# ProProject_stm32f103c8t6__2024-05-02.net
KiCad netlist of a schematic drawn in EasyEDA Pro
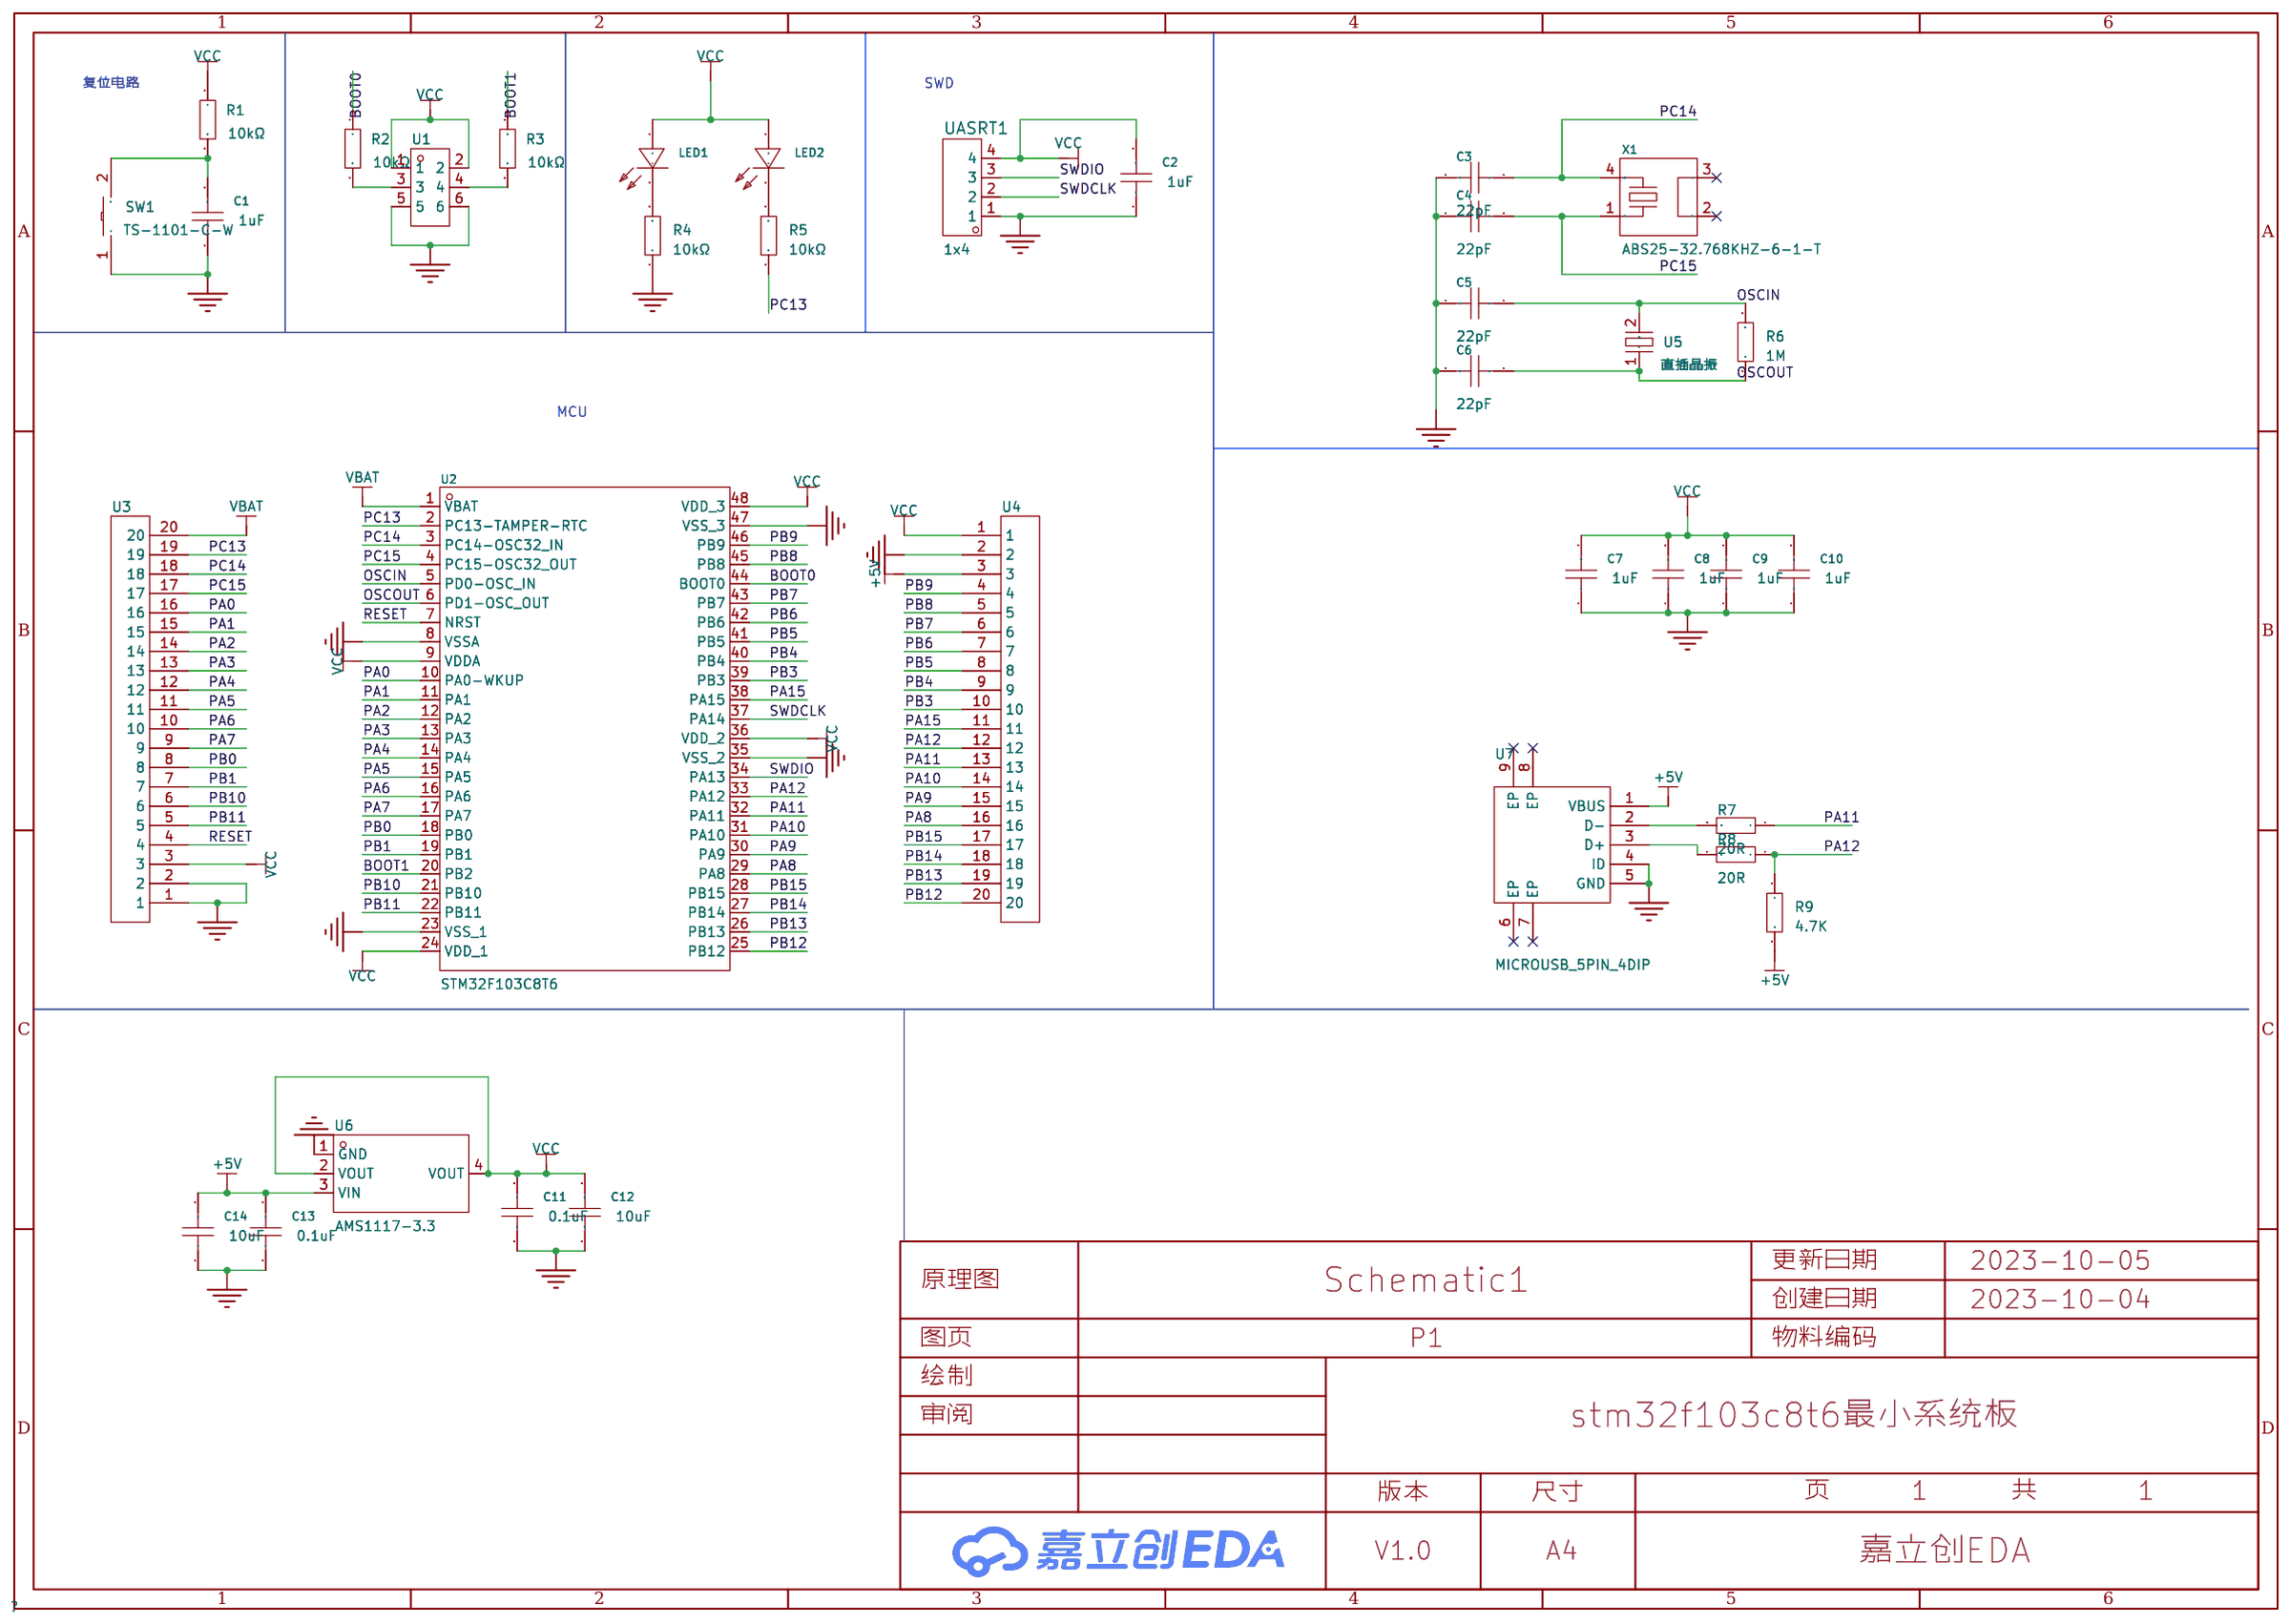
[diagram p0: schematic sheet]

(export (version "E")
  (design (tool "Eeschema 10.0.6"))
  (components
    (comp (ref "C1")
      (value "1uF")
      (footprint "easyedapro:C0603")
      (description "容值:4.7uF;额定电压:25V;材质(温度系数):X5R;")
      (fields
        (field (name "Manufacturer Part") "TCC0603X5R475K250CT")
        (field (name "Manufacturer") "CCTC(三环)")
      )
      (libsource (lib "easyedapro") (part "TCC0603X5R475K250CT"))
    )
    (comp (ref "C2")
      (value "1uF")
      (footprint "easyedapro:C0603")
      (description "容值:4.7uF;额定电压:25V;材质(温度系数):X5R;")
      (fields
        (field (name "Manufacturer Part") "TCC0603X5R475K250CT")
        (field (name "Manufacturer") "CCTC(三环)")
      )
      (libsource (lib "easyedapro") (part "TCC0603X5R475K250CT"))
    )
    (comp (ref "C3")
      (value "22pF")
      (footprint "easyedapro:C0603")
      (description "容值:4.7uF;额定电压:25V;材质(温度系数):X5R;")
      (fields
        (field (name "Manufacturer Part") "TCC0603X5R475K250CT")
        (field (name "Manufacturer") "CCTC(三环)")
      )
      (libsource (lib "easyedapro") (part "TCC0603X5R475K250CT"))
    )
    (comp (ref "C4")
      (value "22pF")
      (footprint "easyedapro:C0603")
      (description "容值:4.7uF;额定电压:25V;材质(温度系数):X5R;")
      (fields
        (field (name "Manufacturer Part") "TCC0603X5R475K250CT")
        (field (name "Manufacturer") "CCTC(三环)")
      )
      (libsource (lib "easyedapro") (part "TCC0603X5R475K250CT"))
    )
    (comp (ref "C5")
      (value "22pF")
      (footprint "easyedapro:C0603")
      (description "容值:4.7uF;额定电压:25V;材质(温度系数):X5R;")
      (fields
        (field (name "Manufacturer Part") "TCC0603X5R475K250CT")
        (field (name "Manufacturer") "CCTC(三环)")
      )
      (libsource (lib "easyedapro") (part "TCC0603X5R475K250CT"))
    )
    (comp (ref "C6")
      (value "22pF")
      (footprint "easyedapro:C0603")
      (description "容值:4.7uF;额定电压:25V;材质(温度系数):X5R;")
      (fields
        (field (name "Manufacturer Part") "TCC0603X5R475K250CT")
        (field (name "Manufacturer") "CCTC(三环)")
      )
      (libsource (lib "easyedapro") (part "TCC0603X5R475K250CT"))
    )
    (comp (ref "C7")
      (value "1uF")
      (footprint "easyedapro:C0603")
      (description "容值:4.7uF;额定电压:25V;材质(温度系数):X5R;")
      (fields
        (field (name "Manufacturer Part") "TCC0603X5R475K250CT")
        (field (name "Manufacturer") "CCTC(三环)")
      )
      (libsource (lib "easyedapro") (part "TCC0603X5R475K250CT"))
    )
    (comp (ref "C8")
      (value "1uF")
      (footprint "easyedapro:C0603")
      (description "容值:4.7uF;额定电压:25V;材质(温度系数):X5R;")
      (fields
        (field (name "Manufacturer Part") "TCC0603X5R475K250CT")
        (field (name "Manufacturer") "CCTC(三环)")
      )
      (libsource (lib "easyedapro") (part "TCC0603X5R475K250CT"))
    )
    (comp (ref "C9")
      (value "1uF")
      (footprint "easyedapro:C0603")
      (description "容值:4.7uF;额定电压:25V;材质(温度系数):X5R;")
      (fields
        (field (name "Manufacturer Part") "TCC0603X5R475K250CT")
        (field (name "Manufacturer") "CCTC(三环)")
      )
      (libsource (lib "easyedapro") (part "TCC0603X5R475K250CT"))
    )
    (comp (ref "C10")
      (value "1uF")
      (footprint "easyedapro:C0603")
      (description "容值:4.7uF;额定电压:25V;材质(温度系数):X5R;")
      (fields
        (field (name "Manufacturer Part") "TCC0603X5R475K250CT")
        (field (name "Manufacturer") "CCTC(三环)")
      )
      (libsource (lib "easyedapro") (part "TCC0603X5R475K250CT"))
    )
    (comp (ref "C11")
      (value "0.1uF")
      (footprint "easyedapro:C0603")
      (description "容值:4.7uF;额定电压:25V;材质(温度系数):X5R;")
      (fields
        (field (name "Manufacturer Part") "TCC0603X5R475K250CT")
        (field (name "Manufacturer") "CCTC(三环)")
      )
      (libsource (lib "easyedapro") (part "TCC0603X5R475K250CT"))
    )
    (comp (ref "C12")
      (value "10uF")
      (footprint "easyedapro:C0603")
      (description "容值:4.7uF;额定电压:25V;材质(温度系数):X5R;")
      (fields
        (field (name "Manufacturer Part") "TCC0603X5R475K250CT")
        (field (name "Manufacturer") "CCTC(三环)")
      )
      (libsource (lib "easyedapro") (part "TCC0603X5R475K250CT"))
    )
    (comp (ref "C13")
      (value "0.1uF")
      (footprint "easyedapro:C0603")
      (description "容值:4.7uF;额定电压:25V;材质(温度系数):X5R;")
      (fields
        (field (name "Manufacturer Part") "TCC0603X5R475K250CT")
        (field (name "Manufacturer") "CCTC(三环)")
      )
      (libsource (lib "easyedapro") (part "TCC0603X5R475K250CT"))
    )
    (comp (ref "C14")
      (value "10uF")
      (footprint "easyedapro:C0603")
      (description "容值:4.7uF;额定电压:25V;材质(温度系数):X5R;")
      (fields
        (field (name "Manufacturer Part") "TCC0603X5R475K250CT")
        (field (name "Manufacturer") "CCTC(三环)")
      )
      (libsource (lib "easyedapro") (part "TCC0603X5R475K250CT"))
    )
    (comp (ref "LED1")
      (value "KT-0805G")
      (footprint "easyedapro:LED0805-R-RD")
      (description "发光颜色:翠绿;二极管配置:-;透镜颜色:-;主波长:-;色温:-;光通量(25℃时):-;发光强度:-;功率:-;发光角度:-;安装方式:-;工作温度:-;")
      (fields (field (name "Manufacturer") "KENTO"))
      (libsource (lib "easyedapro") (part "0805G (Green)"))
    )
    (comp (ref "LED2")
      (value "KT-0805G")
      (footprint "easyedapro:LED0805-R-RD")
      (description "发光颜色:翠绿;二极管配置:-;透镜颜色:-;主波长:-;色温:-;光通量(25°C时):-;发光强度:-;功率:-;发光角度:-;安装方式:-;工作温度:-;")
      (fields (field (name "Manufacturer") "KENTO"))
      (libsource (lib "easyedapro") (part "0805G (Green)"))
    )
    (comp (ref "R1")
      (value "10kΩ")
      (footprint "easyedapro:R0603")
      (description "电阻类型:厚膜电阻;阻值:10kΩ;精度:±1%;功率:100mW;")
      (fields
        (field (name "Manufacturer Part") "0603WAF1002T5E")
        (field (name "Manufacturer") "UNI-ROYAL(厚声)")
      )
      (libsource (lib "easyedapro") (part "0603WAF1002T5E"))
    )
    (comp (ref "R2")
      (value "10kΩ")
      (footprint "easyedapro:R0603")
      (description "电阻类型:厚膜电阻;阻值:10kΩ;精度:±1%;功率:100mW;")
      (fields
        (field (name "Manufacturer Part") "0603WAF1002T5E")
        (field (name "Manufacturer") "UNI-ROYAL(厚声)")
      )
      (libsource (lib "easyedapro") (part "0603WAF1002T5E"))
    )
    (comp (ref "R3")
      (value "10kΩ")
      (footprint "easyedapro:R0603")
      (description "电阻类型:厚膜电阻;阻值:10kΩ;精度:±1%;功率:100mW;")
      (fields
        (field (name "Manufacturer Part") "0603WAF1002T5E")
        (field (name "Manufacturer") "UNI-ROYAL(厚声)")
      )
      (libsource (lib "easyedapro") (part "0603WAF1002T5E"))
    )
    (comp (ref "R4")
      (value "10kΩ")
      (footprint "easyedapro:R0603")
      (description "电阻类型:厚膜电阻;阻值:10kΩ;精度:±1%;功率:100mW;")
      (fields
        (field (name "Manufacturer Part") "0603WAF1002T5E")
        (field (name "Manufacturer") "UNI-ROYAL(厚声)")
      )
      (libsource (lib "easyedapro") (part "0603WAF1002T5E"))
    )
    (comp (ref "R5")
      (value "10kΩ")
      (footprint "easyedapro:R0603")
      (description "电阻类型:厚膜电阻;阻值:10kΩ;精度:±1%;功率:100mW;")
      (fields
        (field (name "Manufacturer Part") "0603WAF1002T5E")
        (field (name "Manufacturer") "UNI-ROYAL(厚声)")
      )
      (libsource (lib "easyedapro") (part "0603WAF1002T5E"))
    )
    (comp (ref "R6")
      (value "1M")
      (footprint "easyedapro:R0603")
      (description "电阻类型:厚膜电阻;阻值:10kΩ;精度:±1%;功率:100mW;")
      (fields
        (field (name "Manufacturer Part") "0603WAF1002T5E")
        (field (name "Manufacturer") "UNI-ROYAL(厚声)")
      )
      (libsource (lib "easyedapro") (part "0603WAF1002T5E"))
    )
    (comp (ref "R7")
      (value "20R")
      (footprint "easyedapro:R0603")
      (description "电阻类型:厚膜电阻;阻值:10kΩ;精度:±1%;功率:100mW;")
      (fields
        (field (name "Manufacturer Part") "0603WAF1002T5E")
        (field (name "Manufacturer") "UNI-ROYAL(厚声)")
      )
      (libsource (lib "easyedapro") (part "0603WAF1002T5E"))
    )
    (comp (ref "R8")
      (value "20R")
      (footprint "easyedapro:R0603")
      (description "电阻类型:厚膜电阻;阻值:10kΩ;精度:±1%;功率:100mW;")
      (fields
        (field (name "Manufacturer Part") "0603WAF1002T5E")
        (field (name "Manufacturer") "UNI-ROYAL(厚声)")
      )
      (libsource (lib "easyedapro") (part "0603WAF1002T5E"))
    )
    (comp (ref "R9")
      (value "4.7K")
      (footprint "easyedapro:R0603")
      (description "电阻类型:厚膜电阻;阻值:10kΩ;精度:±1%;功率:100mW;")
      (fields
        (field (name "Manufacturer Part") "0603WAF1002T5E")
        (field (name "Manufacturer") "UNI-ROYAL(厚声)")
      )
      (libsource (lib "easyedapro") (part "0603WAF1002T5E"))
    )
    (comp (ref "SW1")
      (value "TS-1101-C-W")
      (footprint "easyedapro:SW-SMD_L6.0-W3.3-LS8.0")
      (description "触点电流:50mA;额定电压(AC):-;额定电压(DC):12V;额定功率:-;绝缘电阻:-;电路结构:单刀单掷;安装方式:立贴;带灯:无;作用力:260gf;机械寿命:5万次;带支架:否;")
      (fields (field (name "Manufacturer") "XKB Connectivity(中国星坤)"))
      (libsource (lib "easyedapro") (part "TS-1101-C-W"))
    )
    (comp (ref "U1")
      (value "2.54mm,2X3,短针针长3mm,长针针长6mm")
      (footprint "easyedapro:HDR-TH_6P-P2.54-V-M-R2-C3-S2.54-2")
      (libsource (lib "easyedapro") (part "2.54MM,2X3,短针针长3MM,长针针长6MM"))
    )
    (comp (ref "U2")
      (value "STM32F103C8T6")
      (footprint "easyedapro:LQFP-48_L7.0-W7.0-P0.50-LS9.0-BL")
      (fields (field (name "Manufacturer") "ST(意法半导体)"))
      (libsource (lib "easyedapro") (part "STM32F103C8T6"))
    )
    (comp (ref "U3")
      (value "~")
      (footprint "easyedapro:HDR1X20")
      (libsource (lib "easyedapro") (part "1X20"))
    )
    (comp (ref "U4")
      (value "~")
      (footprint "easyedapro:HDR1X20")
      (libsource (lib "easyedapro") (part "1X20"))
    )
    (comp (ref "U5")
      (value "直插晶振")
      (footprint "easyedapro:HC-49S_L11.0-W4.7-P4.88")
      (libsource (lib "easyedapro") (part "直插晶振"))
    )
    (comp (ref "U6")
      (value "AMS1117-3.3")
      (footprint "easyedapro:SOT-223-3_L6.5-W3.4-P2.30-LS7.0-BR")
      (description "输出类型:固定;输出极性:正;最大输入电压:-;输出电压:3.3V;输出电流:1A;电源纹波抑制比(PSRR):72dB@(120Hz);")
      (fields (field (name "Manufacturer") "AMS"))
      (libsource (lib "easyedapro") (part "AMS1117-3.3"))
    )
    (comp (ref "U7")
      (value "MICROUSB_5PIN_4DIP")
      (footprint "easyedapro:MICRO-USB-SMD_U254-051N-4BH806")
      (libsource (lib "easyedapro") (part "MICROUSB_5PIN_4DIP"))
    )
    (comp (ref "UASRT1")
      (value "1x4")
      (footprint "easyedapro:HDR-TH_4P-P2.54-V-M-1")
      (fields
        (field (name "Manufacturer Part") "Headers  Pins 1*4P")
        (field (name "Manufacturer") "ReliaPro")
      )
      (libsource (lib "easyedapro") (part "1x4"))
    )
    (comp (ref "X1")
      (value "ABS25-32.768KHZ-6-1-T")
      (footprint "easyedapro:SOJ-4_L8.4-W3.8-P5.5-BL")
      (fields (field (name "Manufacturer") "ABRACON"))
      (libsource (lib "easyedapro") (part "ABS25-32.768KHZ-6-1-T"))
    )
  )
  (nets
    (net (code "1") (name "+5V") (class "Default")
      (node (ref "C13") (pin "2") (pinfunction "2_2") (pintype "input"))
      (node (ref "C14") (pin "2") (pinfunction "2_2") (pintype "input"))
      (node (ref "R9") (pin "2") (pinfunction "2_2") (pintype "input"))
      (node (ref "U4") (pin "3") (pinfunction "3_3") (pintype "input"))
      (node (ref "U6") (pin "3") (pinfunction "VIN_3") (pintype "input"))
      (node (ref "U7") (pin "1") (pinfunction "VBUS_1") (pintype "input"))
    )
    (net (code "2") (name "/BOOT0") (class "Default")
      (node (ref "R2") (pin "1") (pinfunction "1_1") (pintype "input"))
      (node (ref "U2") (pin "44") (pinfunction "BOOT0_44") (pintype "input"))
    )
    (net (code "3") (name "/BOOT1") (class "Default")
      (node (ref "R3") (pin "1") (pinfunction "1_1") (pintype "input"))
      (node (ref "U2") (pin "20") (pinfunction "PB2_20") (pintype "input"))
    )
    (net (code "4") (name "/OSCIN") (class "Default")
      (node (ref "C5") (pin "1") (pinfunction "1_1") (pintype "input"))
      (node (ref "R6") (pin "2") (pinfunction "2_2") (pintype "input"))
      (node (ref "U2") (pin "5") (pinfunction "PD0-OSC_IN_5") (pintype "input"))
      (node (ref "U5") (pin "2") (pinfunction "GND_2") (pintype "input"))
    )
    (net (code "5") (name "/OSCOUT") (class "Default")
      (node (ref "C6") (pin "1") (pinfunction "1_1") (pintype "input"))
      (node (ref "R6") (pin "1") (pinfunction "1_1") (pintype "input"))
      (node (ref "U2") (pin "6") (pinfunction "PD1-OSC_OUT_6") (pintype "input"))
      (node (ref "U5") (pin "1") (pinfunction "1_1") (pintype "input"))
    )
    (net (code "6") (name "/PA0") (class "Default")
      (node (ref "U2") (pin "10") (pinfunction "PA0-WKUP_10") (pintype "input"))
      (node (ref "U3") (pin "16") (pinfunction "16_16") (pintype "input"))
    )
    (net (code "7") (name "/PA1") (class "Default")
      (node (ref "U2") (pin "11") (pinfunction "PA1_11") (pintype "input"))
      (node (ref "U3") (pin "15") (pinfunction "15_15") (pintype "input"))
    )
    (net (code "8") (name "/PA2") (class "Default")
      (node (ref "U2") (pin "12") (pinfunction "PA2_12") (pintype "input"))
      (node (ref "U3") (pin "14") (pinfunction "14_14") (pintype "input"))
    )
    (net (code "9") (name "/PA3") (class "Default")
      (node (ref "U2") (pin "13") (pinfunction "PA3_13") (pintype "input"))
      (node (ref "U3") (pin "13") (pinfunction "13_13") (pintype "input"))
    )
    (net (code "10") (name "/PA4") (class "Default")
      (node (ref "U2") (pin "14") (pinfunction "PA4_14") (pintype "input"))
      (node (ref "U3") (pin "12") (pinfunction "12_12") (pintype "input"))
    )
    (net (code "11") (name "/PA5") (class "Default")
      (node (ref "U2") (pin "15") (pinfunction "PA5_15") (pintype "input"))
      (node (ref "U3") (pin "11") (pinfunction "11_11") (pintype "input"))
    )
    (net (code "12") (name "/PA6") (class "Default")
      (node (ref "U2") (pin "16") (pinfunction "PA6_16") (pintype "input"))
      (node (ref "U3") (pin "10") (pinfunction "10_10") (pintype "input"))
    )
    (net (code "13") (name "/PA7") (class "Default")
      (node (ref "U2") (pin "17") (pinfunction "PA7_17") (pintype "input"))
      (node (ref "U3") (pin "9") (pinfunction "9_9") (pintype "input"))
    )
    (net (code "14") (name "/PA8") (class "Default")
      (node (ref "U2") (pin "29") (pinfunction "PA8_29") (pintype "input"))
      (node (ref "U4") (pin "16") (pinfunction "16_16") (pintype "input"))
    )
    (net (code "15") (name "/PA9") (class "Default")
      (node (ref "U2") (pin "30") (pinfunction "PA9_30") (pintype "input"))
      (node (ref "U4") (pin "15") (pinfunction "15_15") (pintype "input"))
    )
    (net (code "16") (name "/PA10") (class "Default")
      (node (ref "U2") (pin "31") (pinfunction "PA10_31") (pintype "input"))
      (node (ref "U4") (pin "14") (pinfunction "14_14") (pintype "input"))
    )
    (net (code "17") (name "/PA11") (class "Default")
      (node (ref "R7") (pin "1") (pinfunction "1_1") (pintype "input"))
      (node (ref "U2") (pin "32") (pinfunction "PA11_32") (pintype "input"))
      (node (ref "U4") (pin "13") (pinfunction "13_13") (pintype "input"))
    )
    (net (code "18") (name "/PA12") (class "Default")
      (node (ref "R8") (pin "1") (pinfunction "1_1") (pintype "input"))
      (node (ref "R9") (pin "1") (pinfunction "1_1") (pintype "input"))
      (node (ref "U2") (pin "33") (pinfunction "PA12_33") (pintype "input"))
      (node (ref "U4") (pin "12") (pinfunction "12_12") (pintype "input"))
    )
    (net (code "19") (name "/PA15") (class "Default")
      (node (ref "U2") (pin "38") (pinfunction "PA15_38") (pintype "input"))
      (node (ref "U4") (pin "11") (pinfunction "11_11") (pintype "input"))
    )
    (net (code "20") (name "/PB0") (class "Default")
      (node (ref "U2") (pin "18") (pinfunction "PB0_18") (pintype "input"))
      (node (ref "U3") (pin "8") (pinfunction "8_8") (pintype "input"))
    )
    (net (code "21") (name "/PB1") (class "Default")
      (node (ref "U2") (pin "19") (pinfunction "PB1_19") (pintype "input"))
      (node (ref "U3") (pin "7") (pinfunction "7_7") (pintype "input"))
    )
    (net (code "22") (name "/PB3") (class "Default")
      (node (ref "U2") (pin "39") (pinfunction "PB3_39") (pintype "input"))
      (node (ref "U4") (pin "10") (pinfunction "10_10") (pintype "input"))
    )
    (net (code "23") (name "/PB4") (class "Default")
      (node (ref "U2") (pin "40") (pinfunction "PB4_40") (pintype "input"))
      (node (ref "U4") (pin "9") (pinfunction "9_9") (pintype "input"))
    )
    (net (code "24") (name "/PB5") (class "Default")
      (node (ref "U2") (pin "41") (pinfunction "PB5_41") (pintype "input"))
      (node (ref "U4") (pin "8") (pinfunction "8_8") (pintype "input"))
    )
    (net (code "25") (name "/PB6") (class "Default")
      (node (ref "U2") (pin "42") (pinfunction "PB6_42") (pintype "input"))
      (node (ref "U4") (pin "7") (pinfunction "7_7") (pintype "input"))
    )
    (net (code "26") (name "/PB7") (class "Default")
      (node (ref "U2") (pin "43") (pinfunction "PB7_43") (pintype "input"))
      (node (ref "U4") (pin "6") (pinfunction "6_6") (pintype "input"))
    )
    (net (code "27") (name "/PB8") (class "Default")
      (node (ref "U2") (pin "45") (pinfunction "PB8_45") (pintype "input"))
      (node (ref "U4") (pin "5") (pinfunction "5_5") (pintype "input"))
    )
    (net (code "28") (name "/PB9") (class "Default")
      (node (ref "U2") (pin "46") (pinfunction "PB9_46") (pintype "input"))
      (node (ref "U4") (pin "4") (pinfunction "4_4") (pintype "input"))
    )
    (net (code "29") (name "/PB10") (class "Default")
      (node (ref "U2") (pin "21") (pinfunction "PB10_21") (pintype "input"))
      (node (ref "U3") (pin "6") (pinfunction "6_6") (pintype "input"))
    )
    (net (code "30") (name "/PB11") (class "Default")
      (node (ref "U2") (pin "22") (pinfunction "PB11_22") (pintype "input"))
      (node (ref "U3") (pin "5") (pinfunction "5_5") (pintype "input"))
    )
    (net (code "31") (name "/PB12") (class "Default")
      (node (ref "U2") (pin "25") (pinfunction "PB12_25") (pintype "input"))
      (node (ref "U4") (pin "20") (pinfunction "20_20") (pintype "input"))
    )
    (net (code "32") (name "/PB13") (class "Default")
      (node (ref "U2") (pin "26") (pinfunction "PB13_26") (pintype "input"))
      (node (ref "U4") (pin "19") (pinfunction "19_19") (pintype "input"))
    )
    (net (code "33") (name "/PB14") (class "Default")
      (node (ref "U2") (pin "27") (pinfunction "PB14_27") (pintype "input"))
      (node (ref "U4") (pin "18") (pinfunction "18_18") (pintype "input"))
    )
    (net (code "34") (name "/PB15") (class "Default")
      (node (ref "U2") (pin "28") (pinfunction "PB15_28") (pintype "input"))
      (node (ref "U4") (pin "17") (pinfunction "17_17") (pintype "input"))
    )
    (net (code "35") (name "/PC13") (class "Default")
      (node (ref "R5") (pin "1") (pinfunction "1_1") (pintype "input"))
      (node (ref "U2") (pin "2") (pinfunction "PC13-TAMPER-RTC_2") (pintype "input"))
      (node (ref "U3") (pin "19") (pinfunction "19_19") (pintype "input"))
    )
    (net (code "36") (name "/PC14") (class "Default")
      (node (ref "C3") (pin "1") (pinfunction "1_1") (pintype "input"))
      (node (ref "U2") (pin "3") (pinfunction "PC14-OSC32_IN_3") (pintype "input"))
      (node (ref "U3") (pin "18") (pinfunction "18_18") (pintype "input"))
      (node (ref "X1") (pin "4") (pinfunction "GND_4") (pintype "input"))
    )
    (net (code "37") (name "/PC15") (class "Default")
      (node (ref "C4") (pin "1") (pinfunction "1_1") (pintype "input"))
      (node (ref "U2") (pin "4") (pinfunction "PC15-OSC32_OUT_4") (pintype "input"))
      (node (ref "U3") (pin "17") (pinfunction "17_17") (pintype "input"))
      (node (ref "X1") (pin "1") (pinfunction "1_1") (pintype "input"))
    )
    (net (code "38") (name "/RESET") (class "Default")
      (node (ref "U2") (pin "7") (pinfunction "NRST_7") (pintype "input"))
      (node (ref "U3") (pin "4") (pinfunction "4_4") (pintype "input"))
    )
    (net (code "39") (name "/SWDCLK") (class "Default")
      (node (ref "U2") (pin "37") (pinfunction "PA14_37") (pintype "input"))
      (node (ref "UASRT1") (pin "2") (pinfunction "2_2") (pintype "input"))
    )
    (net (code "40") (name "/SWDIO") (class "Default")
      (node (ref "U2") (pin "34") (pinfunction "PA13_34") (pintype "input"))
      (node (ref "UASRT1") (pin "3") (pinfunction "3_3") (pintype "input"))
    )
    (net (code "41") (name "GND") (class "Default")
      (node (ref "C1") (pin "1") (pinfunction "1_1") (pintype "input"))
      (node (ref "C10") (pin "1") (pinfunction "1_1") (pintype "input"))
      (node (ref "C11") (pin "1") (pinfunction "1_1") (pintype "input"))
      (node (ref "C12") (pin "1") (pinfunction "1_1") (pintype "input"))
      (node (ref "C13") (pin "1") (pinfunction "1_1") (pintype "input"))
      (node (ref "C14") (pin "1") (pinfunction "1_1") (pintype "input"))
      (node (ref "C2") (pin "1") (pinfunction "1_1") (pintype "input"))
      (node (ref "C3") (pin "2") (pinfunction "2_2") (pintype "input"))
      (node (ref "C4") (pin "2") (pinfunction "2_2") (pintype "input"))
      (node (ref "C5") (pin "2") (pinfunction "2_2") (pintype "input"))
      (node (ref "C6") (pin "2") (pinfunction "2_2") (pintype "input"))
      (node (ref "C7") (pin "1") (pinfunction "1_1") (pintype "input"))
      (node (ref "C8") (pin "1") (pinfunction "1_1") (pintype "input"))
      (node (ref "C9") (pin "1") (pinfunction "1_1") (pintype "input"))
      (node (ref "R4") (pin "1") (pinfunction "1_1") (pintype "input"))
      (node (ref "SW1") (pin "1") (pinfunction "1_1") (pintype "input"))
      (node (ref "U1") (pin "5") (pinfunction "5_5") (pintype "input"))
      (node (ref "U1") (pin "6") (pinfunction "6_6") (pintype "input"))
      (node (ref "U2") (pin "23") (pinfunction "VSS_1_23") (pintype "input"))
      (node (ref "U2") (pin "35") (pinfunction "VSS_2_35") (pintype "input"))
      (node (ref "U2") (pin "47") (pinfunction "VSS_3_47") (pintype "input"))
      (node (ref "U2") (pin "8") (pinfunction "VSSA_8") (pintype "input"))
      (node (ref "U3") (pin "1") (pinfunction "1_1") (pintype "input"))
      (node (ref "U3") (pin "2") (pinfunction "2_2") (pintype "input"))
      (node (ref "U4") (pin "2") (pinfunction "2_2") (pintype "input"))
      (node (ref "U6") (pin "1") (pinfunction "GND_1") (pintype "input"))
      (node (ref "U7") (pin "4") (pinfunction "ID_4") (pintype "input"))
      (node (ref "U7") (pin "5") (pinfunction "GND_5") (pintype "input"))
      (node (ref "UASRT1") (pin "1") (pinfunction "1_1") (pintype "input"))
    )
    (net (code "42") (name "Net-(C1-Pad2)") (class "Default")
      (node (ref "C1") (pin "2") (pinfunction "2_2") (pintype "input"))
      (node (ref "R1") (pin "2") (pinfunction "2_2") (pintype "input"))
      (node (ref "SW1") (pin "2") (pinfunction "2_2") (pintype "input"))
    )
    (net (code "43") (name "Net-(LED1-K)") (class "Default")
      (node (ref "LED1") (pin "2") (pinfunction "K_2") (pintype "input"))
      (node (ref "R4") (pin "2") (pinfunction "2_2") (pintype "input"))
    )
    (net (code "44") (name "Net-(LED2-K)") (class "Default")
      (node (ref "LED2") (pin "2") (pinfunction "K_2") (pintype "input"))
      (node (ref "R5") (pin "2") (pinfunction "2_2") (pintype "input"))
    )
    (net (code "45") (name "Net-(R2-Pad2)") (class "Default")
      (node (ref "R2") (pin "2") (pinfunction "2_2") (pintype "input"))
      (node (ref "U1") (pin "3") (pinfunction "3_3") (pintype "input"))
    )
    (net (code "46") (name "Net-(R3-Pad2)") (class "Default")
      (node (ref "R3") (pin "2") (pinfunction "2_2") (pintype "input"))
      (node (ref "U1") (pin "4") (pinfunction "4_4") (pintype "input"))
    )
    (net (code "47") (name "Net-(U7-D+)") (class "Default")
      (node (ref "R8") (pin "2") (pinfunction "2_2") (pintype "input"))
      (node (ref "U7") (pin "3") (pinfunction "D+_3") (pintype "input"))
    )
    (net (code "48") (name "Net-(U7-D-)") (class "Default")
      (node (ref "R7") (pin "2") (pinfunction "2_2") (pintype "input"))
      (node (ref "U7") (pin "2") (pinfunction "D-_2") (pintype "input"))
    )
    (net (code "49") (name "VBAT") (class "Default")
      (node (ref "U2") (pin "1") (pinfunction "VBAT_1") (pintype "input"))
      (node (ref "U3") (pin "20") (pinfunction "20_20") (pintype "input"))
    )
    (net (code "50") (name "VCC") (class "Default")
      (node (ref "C10") (pin "2") (pinfunction "2_2") (pintype "input"))
      (node (ref "C11") (pin "2") (pinfunction "2_2") (pintype "input"))
      (node (ref "C12") (pin "2") (pinfunction "2_2") (pintype "input"))
      (node (ref "C2") (pin "2") (pinfunction "2_2") (pintype "input"))
      (node (ref "C7") (pin "2") (pinfunction "2_2") (pintype "input"))
      (node (ref "C8") (pin "2") (pinfunction "2_2") (pintype "input"))
      (node (ref "C9") (pin "2") (pinfunction "2_2") (pintype "input"))
      (node (ref "LED1") (pin "1") (pinfunction "A_1") (pintype "input"))
      (node (ref "LED2") (pin "1") (pinfunction "A_1") (pintype "input"))
      (node (ref "R1") (pin "1") (pinfunction "1_1") (pintype "input"))
      (node (ref "U1") (pin "1") (pinfunction "1_1") (pintype "input"))
      (node (ref "U1") (pin "2") (pinfunction "2_2") (pintype "input"))
      (node (ref "U2") (pin "24") (pinfunction "VDD_1_24") (pintype "input"))
      (node (ref "U2") (pin "36") (pinfunction "VDD_2_36") (pintype "input"))
      (node (ref "U2") (pin "48") (pinfunction "VDD_3_48") (pintype "input"))
      (node (ref "U2") (pin "9") (pinfunction "VDDA_9") (pintype "input"))
      (node (ref "U3") (pin "3") (pinfunction "3_3") (pintype "input"))
      (node (ref "U4") (pin "1") (pinfunction "1_1") (pintype "input"))
      (node (ref "U6") (pin "2") (pinfunction "VOUT_2") (pintype "input"))
      (node (ref "U6") (pin "4") (pinfunction "VOUT_4") (pintype "input"))
      (node (ref "UASRT1") (pin "4") (pinfunction "4_4") (pintype "input"))
    )
    (net (code "51") (name "unconnected-(U7-EP-Pad6)") (class "Default")
      (node (ref "U7") (pin "6") (pinfunction "EP_6") (pintype "input+no_connect"))
    )
    (net (code "52") (name "unconnected-(U7-EP-Pad7)") (class "Default")
      (node (ref "U7") (pin "7") (pinfunction "EP_7") (pintype "input+no_connect"))
    )
    (net (code "53") (name "unconnected-(U7-EP-Pad8)") (class "Default")
      (node (ref "U7") (pin "8") (pinfunction "EP_8") (pintype "input+no_connect"))
    )
    (net (code "54") (name "unconnected-(U7-EP-Pad9)") (class "Default")
      (node (ref "U7") (pin "9") (pinfunction "EP_9") (pintype "input+no_connect"))
    )
    (net (code "55") (name "unconnected-(X1-GND-Pad2)") (class "Default")
      (node (ref "X1") (pin "2") (pinfunction "GND_2") (pintype "input+no_connect"))
    )
    (net (code "56") (name "unconnected-(X1-Pad3)") (class "Default")
      (node (ref "X1") (pin "3") (pinfunction "3_3") (pintype "input+no_connect"))
    )
  )
)
